# 9-Dof_Sensor_Card.net
KiCad netlist of a schematic drawn in EAGLE
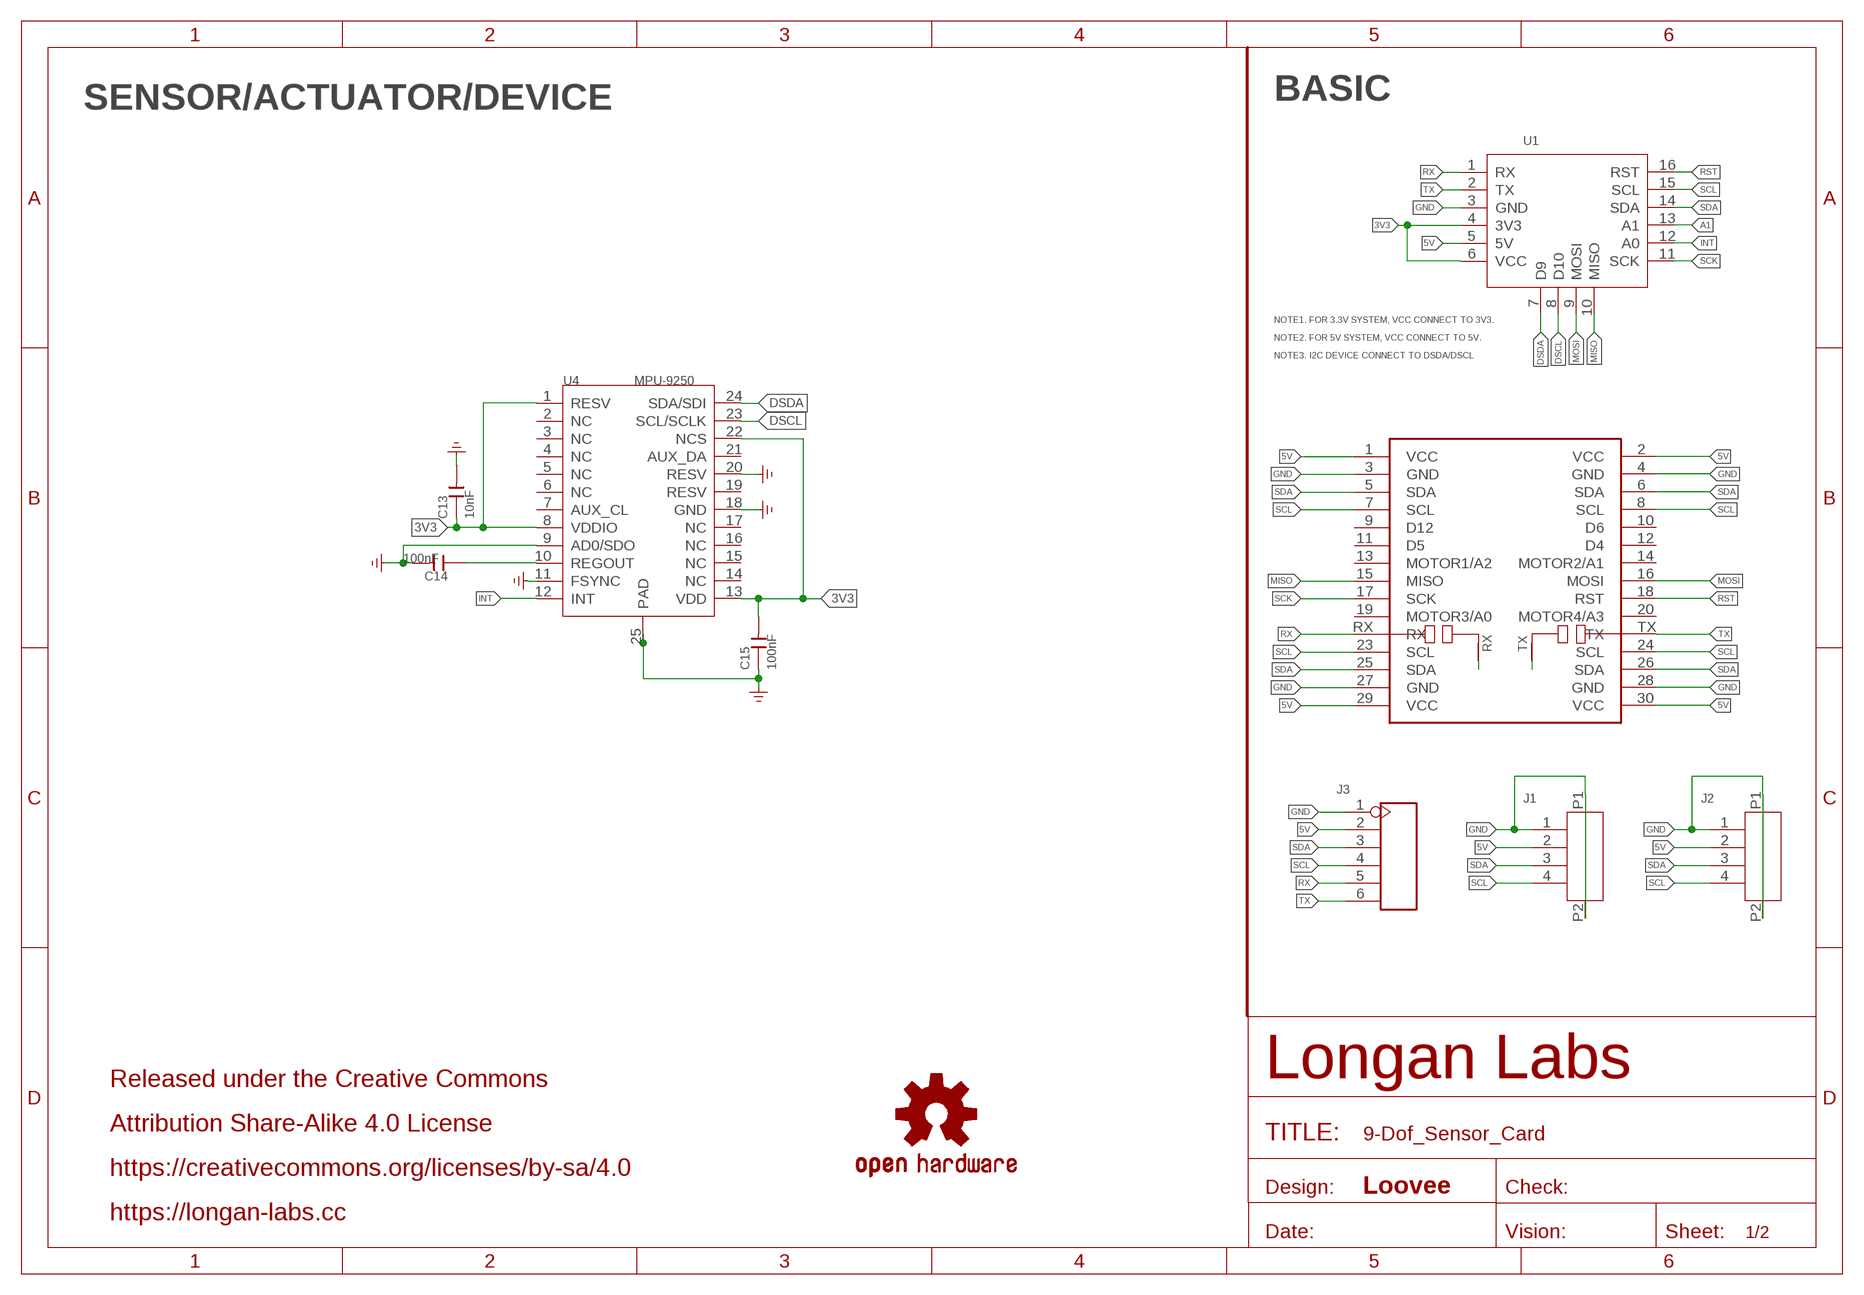
[diagram p0: schematic, sheet 1]

(export (version "E")
  (design (tool "Eeschema 10.0.6"))
  (components
    (comp (ref "C13")
      (value "10nF")
      (footprint "eagle-import:C0603")
      (libsource (lib "eagle-import") (part "CAP-0603"))
    )
    (comp (ref "C14")
      (value "100nF")
      (footprint "eagle-import:C0603")
      (libsource (lib "eagle-import") (part "CAP-0603"))
    )
    (comp (ref "C15")
      (value "100nF")
      (footprint "eagle-import:C0603")
      (libsource (lib "eagle-import") (part "CAP-0603"))
    )
    (comp (ref "J1")
      (value "HEADER-4P-1.0")
      (footprint "eagle-import:4P-1.0-90D")
      (libsource (lib "eagle-import") (part "HEADER-4P-1.0"))
    )
    (comp (ref "J2")
      (value "HEADER-4P-1.0")
      (footprint "eagle-import:4P-1.0-90D")
      (libsource (lib "eagle-import") (part "HEADER-4P-1.0"))
    )
    (comp (ref "J3")
      (value "HEADER-6P-55/35MIL")
      (footprint "eagle-import:H6-2.54")
      (libsource (lib "eagle-import") (part "HEADER-6P-55/35MIL"))
    )
    (comp (ref "LOGO2")
      (value "OSHW-LOGOS")
      (footprint "eagle-import:OSHW-LOGO-S")
      (libsource (lib "eagle-import") (part "OSHW-LOGOS"))
    )
    (comp (ref "MOUDLE2")
      (value "MOUDLE-CARDS-UART'BOARD'")
      (footprint "eagle-import:MOUDLE-2X15P-UART")
      (libsource (lib "eagle-import") (part "MOUDLE-CARDS-UART'BOARD'"))
    )
    (comp (ref "U1")
      (value "MOUDLE-CARDS")
      (footprint "eagle-import:16P-2.0-CARDS")
      (libsource (lib "eagle-import") (part "MOUDLE-CARDS"))
    )
    (comp (ref "U4")
      (value "MPU-9250")
      (footprint "eagle-import:LEAD-QFN24")
      (libsource (lib "eagle-import") (part "MPU-9250"))
    )
  )
  (nets
    (net (code "1") (name "3V3") (class "Default")
      (node (ref "C13") (pin "1") (pinfunction "1_1") (pintype "passive"))
      (node (ref "C15") (pin "2") (pinfunction "2_2") (pintype "passive"))
      (node (ref "U1") (pin "4") (pinfunction "3V3_4") (pintype "bidirectional"))
      (node (ref "U1") (pin "6") (pinfunction "VCC_6") (pintype "bidirectional"))
      (node (ref "U4") (pin "1") (pinfunction "RESV_1") (pintype "bidirectional"))
      (node (ref "U4") (pin "13") (pinfunction "VDD_13") (pintype "bidirectional"))
      (node (ref "U4") (pin "22") (pinfunction "NCS_22") (pintype "bidirectional"))
      (node (ref "U4") (pin "8") (pinfunction "VDDIO_8") (pintype "bidirectional"))
    )
    (net (code "2") (name "5V") (class "Default")
      (node (ref "J1") (pin "2") (pinfunction "2_2") (pintype "bidirectional"))
      (node (ref "J2") (pin "2") (pinfunction "2_2") (pintype "bidirectional"))
      (node (ref "J3") (pin "2") (pinfunction "2_2") (pintype "bidirectional"))
      (node (ref "MOUDLE2") (pin "1") (pinfunction "VCC_1") (pintype "bidirectional"))
      (node (ref "MOUDLE2") (pin "2") (pinfunction "VCC_2") (pintype "bidirectional"))
      (node (ref "MOUDLE2") (pin "29") (pinfunction "VCC_29") (pintype "bidirectional"))
      (node (ref "MOUDLE2") (pin "30") (pinfunction "VCC_30") (pintype "bidirectional"))
      (node (ref "U1") (pin "5") (pinfunction "5V_5") (pintype "bidirectional"))
    )
    (net (code "3") (name "A1") (class "Default")
      (node (ref "U1") (pin "13") (pinfunction "A1_13") (pintype "bidirectional"))
    )
    (net (code "4") (name "DSCL") (class "Default")
      (node (ref "U1") (pin "8") (pinfunction "D10_8") (pintype "bidirectional"))
      (node (ref "U4") (pin "23") (pinfunction "SCL/SCLK_23") (pintype "bidirectional"))
    )
    (net (code "5") (name "DSDA") (class "Default")
      (node (ref "U1") (pin "7") (pinfunction "D9_7") (pintype "bidirectional"))
      (node (ref "U4") (pin "24") (pinfunction "SDA/SDI_24") (pintype "bidirectional"))
    )
    (net (code "6") (name "GND") (class "Default")
      (node (ref "C13") (pin "2") (pinfunction "2_2") (pintype "passive"))
      (node (ref "C14") (pin "2") (pinfunction "2_2") (pintype "passive"))
      (node (ref "C15") (pin "1") (pinfunction "1_1") (pintype "passive"))
      (node (ref "J1") (pin "1") (pinfunction "1_1") (pintype "bidirectional"))
      (node (ref "J1") (pin "P1") (pinfunction "P1_P1") (pintype "bidirectional"))
      (node (ref "J1") (pin "P2") (pinfunction "P2_P2") (pintype "bidirectional"))
      (node (ref "J2") (pin "1") (pinfunction "1_1") (pintype "bidirectional"))
      (node (ref "J2") (pin "P1") (pinfunction "P1_P1") (pintype "bidirectional"))
      (node (ref "J2") (pin "P2") (pinfunction "P2_P2") (pintype "bidirectional"))
      (node (ref "J3") (pin "1") (pinfunction "1_1") (pintype "bidirectional"))
      (node (ref "MOUDLE2") (pin "27") (pinfunction "GND_27") (pintype "bidirectional"))
      (node (ref "MOUDLE2") (pin "28") (pinfunction "GND_28") (pintype "bidirectional"))
      (node (ref "MOUDLE2") (pin "3") (pinfunction "GND_3") (pintype "bidirectional"))
      (node (ref "MOUDLE2") (pin "4") (pinfunction "GND_4") (pintype "bidirectional"))
      (node (ref "U1") (pin "3") (pinfunction "GND_3") (pintype "bidirectional"))
      (node (ref "U4") (pin "11") (pinfunction "FSYNC_11") (pintype "bidirectional"))
      (node (ref "U4") (pin "18") (pinfunction "GND_18") (pintype "bidirectional"))
      (node (ref "U4") (pin "20") (pinfunction "RESV_20") (pintype "bidirectional"))
      (node (ref "U4") (pin "25") (pinfunction "PAD_25") (pintype "bidirectional"))
      (node (ref "U4") (pin "9") (pinfunction "AD0/SDO_9") (pintype "bidirectional"))
    )
    (net (code "7") (name "INT") (class "Default")
      (node (ref "U1") (pin "12") (pinfunction "A0_12") (pintype "bidirectional"))
      (node (ref "U4") (pin "12") (pinfunction "INT_12") (pintype "bidirectional"))
    )
    (net (code "8") (name "MISO") (class "Default")
      (node (ref "MOUDLE2") (pin "15") (pinfunction "MISO_15") (pintype "bidirectional"))
      (node (ref "U1") (pin "10") (pinfunction "MISO_10") (pintype "bidirectional"))
    )
    (net (code "9") (name "MOSI") (class "Default")
      (node (ref "MOUDLE2") (pin "16") (pinfunction "MOSI_16") (pintype "bidirectional"))
      (node (ref "U1") (pin "9") (pinfunction "MOSI_9") (pintype "bidirectional"))
    )
    (net (code "10") (name "Net-(MOUDLE2-RX{slash}N-PadRX{slash}N1)") (class "Default")
      (node (ref "MOUDLE2") (pin "RX/N1") (pinfunction "RX/N_RX/N1") (pintype "bidirectional"))
      (node (ref "MOUDLE2") (pin "RX/N2") (pinfunction "RX/N_RX/N2") (pintype "bidirectional"))
    )
    (net (code "11") (name "Net-(MOUDLE2-TX{slash}N-PadTX{slash}N1)") (class "Default")
      (node (ref "MOUDLE2") (pin "TX/N1") (pinfunction "TX/N_TX/N1") (pintype "bidirectional"))
      (node (ref "MOUDLE2") (pin "TX/N2") (pinfunction "TX/N_TX/N2") (pintype "bidirectional"))
    )
    (net (code "12") (name "Net-(U4-REGOUT)") (class "Default")
      (node (ref "C14") (pin "1") (pinfunction "1_1") (pintype "passive"))
      (node (ref "U4") (pin "10") (pinfunction "REGOUT_10") (pintype "bidirectional"))
    )
    (net (code "13") (name "RST") (class "Default")
      (node (ref "MOUDLE2") (pin "18") (pinfunction "RST_18") (pintype "bidirectional"))
      (node (ref "U1") (pin "16") (pinfunction "RST_16") (pintype "bidirectional"))
    )
    (net (code "14") (name "RX") (class "Default")
      (node (ref "J3") (pin "5") (pinfunction "5_5") (pintype "bidirectional"))
      (node (ref "MOUDLE2") (pin "RX") (pinfunction "RX_RX") (pintype "bidirectional"))
      (node (ref "U1") (pin "1") (pinfunction "RX_1") (pintype "bidirectional"))
    )
    (net (code "15") (name "SCK") (class "Default")
      (node (ref "MOUDLE2") (pin "17") (pinfunction "SCK_17") (pintype "bidirectional"))
      (node (ref "U1") (pin "11") (pinfunction "SCK_11") (pintype "bidirectional"))
    )
    (net (code "16") (name "SCL") (class "Default")
      (node (ref "J1") (pin "4") (pinfunction "4_4") (pintype "bidirectional"))
      (node (ref "J2") (pin "4") (pinfunction "4_4") (pintype "bidirectional"))
      (node (ref "J3") (pin "4") (pinfunction "4_4") (pintype "bidirectional"))
      (node (ref "MOUDLE2") (pin "23") (pinfunction "SCL_23") (pintype "bidirectional"))
      (node (ref "MOUDLE2") (pin "24") (pinfunction "SCL_24") (pintype "bidirectional"))
      (node (ref "MOUDLE2") (pin "7") (pinfunction "SCL_7") (pintype "bidirectional"))
      (node (ref "MOUDLE2") (pin "8") (pinfunction "SCL_8") (pintype "bidirectional"))
      (node (ref "U1") (pin "15") (pinfunction "SCL_15") (pintype "bidirectional"))
    )
    (net (code "17") (name "SDA") (class "Default")
      (node (ref "J1") (pin "3") (pinfunction "3_3") (pintype "bidirectional"))
      (node (ref "J2") (pin "3") (pinfunction "3_3") (pintype "bidirectional"))
      (node (ref "J3") (pin "3") (pinfunction "3_3") (pintype "bidirectional"))
      (node (ref "MOUDLE2") (pin "25") (pinfunction "SDA_25") (pintype "bidirectional"))
      (node (ref "MOUDLE2") (pin "26") (pinfunction "SDA_26") (pintype "bidirectional"))
      (node (ref "MOUDLE2") (pin "5") (pinfunction "SDA_5") (pintype "bidirectional"))
      (node (ref "MOUDLE2") (pin "6") (pinfunction "SDA_6") (pintype "bidirectional"))
      (node (ref "U1") (pin "14") (pinfunction "SDA_14") (pintype "bidirectional"))
    )
    (net (code "18") (name "TX") (class "Default")
      (node (ref "J3") (pin "6") (pinfunction "6_6") (pintype "bidirectional"))
      (node (ref "MOUDLE2") (pin "TX") (pinfunction "TX_TX") (pintype "bidirectional"))
      (node (ref "U1") (pin "2") (pinfunction "TX_2") (pintype "bidirectional"))
    )
    (net (code "19") (name "unconnected-(MOUDLE2-D4-Pad12)") (class "Default")
      (node (ref "MOUDLE2") (pin "12") (pinfunction "D4_12") (pintype "bidirectional"))
    )
    (net (code "20") (name "unconnected-(MOUDLE2-D5-Pad11)") (class "Default")
      (node (ref "MOUDLE2") (pin "11") (pinfunction "D5_11") (pintype "bidirectional"))
    )
    (net (code "21") (name "unconnected-(MOUDLE2-D6-Pad10)") (class "Default")
      (node (ref "MOUDLE2") (pin "10") (pinfunction "D6_10") (pintype "bidirectional"))
    )
    (net (code "22") (name "unconnected-(MOUDLE2-D12-Pad9)") (class "Default")
      (node (ref "MOUDLE2") (pin "9") (pinfunction "D12_9") (pintype "bidirectional"))
    )
    (net (code "23") (name "unconnected-(MOUDLE2-MOTOR1{slash}A2-Pad13)") (class "Default")
      (node (ref "MOUDLE2") (pin "13") (pinfunction "MOTOR1/A2_13") (pintype "bidirectional"))
    )
    (net (code "24") (name "unconnected-(MOUDLE2-MOTOR2{slash}A1-Pad14)") (class "Default")
      (node (ref "MOUDLE2") (pin "14") (pinfunction "MOTOR2/A1_14") (pintype "bidirectional"))
    )
    (net (code "25") (name "unconnected-(MOUDLE2-MOTOR3{slash}A0-Pad19)") (class "Default")
      (node (ref "MOUDLE2") (pin "19") (pinfunction "MOTOR3/A0_19") (pintype "bidirectional"))
    )
    (net (code "26") (name "unconnected-(MOUDLE2-MOTOR4{slash}A3-Pad20)") (class "Default")
      (node (ref "MOUDLE2") (pin "20") (pinfunction "MOTOR4/A3_20") (pintype "bidirectional"))
    )
    (net (code "27") (name "unconnected-(U4-AUX_CL-Pad7)") (class "Default")
      (node (ref "U4") (pin "7") (pinfunction "AUX_CL_7") (pintype "bidirectional"))
    )
    (net (code "28") (name "unconnected-(U4-AUX_DA-Pad21)") (class "Default")
      (node (ref "U4") (pin "21") (pinfunction "AUX_DA_21") (pintype "bidirectional"))
    )
    (net (code "29") (name "unconnected-(U4-NC-Pad2)") (class "Default")
      (node (ref "U4") (pin "2") (pinfunction "NC_2") (pintype "bidirectional"))
    )
    (net (code "30") (name "unconnected-(U4-NC-Pad3)") (class "Default")
      (node (ref "U4") (pin "3") (pinfunction "NC_3") (pintype "bidirectional"))
    )
    (net (code "31") (name "unconnected-(U4-NC-Pad4)") (class "Default")
      (node (ref "U4") (pin "4") (pinfunction "NC_4") (pintype "bidirectional"))
    )
    (net (code "32") (name "unconnected-(U4-NC-Pad5)") (class "Default")
      (node (ref "U4") (pin "5") (pinfunction "NC_5") (pintype "bidirectional"))
    )
    (net (code "33") (name "unconnected-(U4-NC-Pad6)") (class "Default")
      (node (ref "U4") (pin "6") (pinfunction "NC_6") (pintype "bidirectional"))
    )
    (net (code "34") (name "unconnected-(U4-NC-Pad14)") (class "Default")
      (node (ref "U4") (pin "14") (pinfunction "NC_14") (pintype "bidirectional"))
    )
    (net (code "35") (name "unconnected-(U4-NC-Pad15)") (class "Default")
      (node (ref "U4") (pin "15") (pinfunction "NC_15") (pintype "bidirectional"))
    )
    (net (code "36") (name "unconnected-(U4-NC-Pad16)") (class "Default")
      (node (ref "U4") (pin "16") (pinfunction "NC_16") (pintype "bidirectional"))
    )
    (net (code "37") (name "unconnected-(U4-NC-Pad17)") (class "Default")
      (node (ref "U4") (pin "17") (pinfunction "NC_17") (pintype "bidirectional"))
    )
    (net (code "38") (name "unconnected-(U4-RESV-Pad19)") (class "Default")
      (node (ref "U4") (pin "19") (pinfunction "RESV_19") (pintype "bidirectional"))
    )
  )
)
